# 7_Sensitivity.net
KiCad netlist of a schematic drawn in Altium Designer
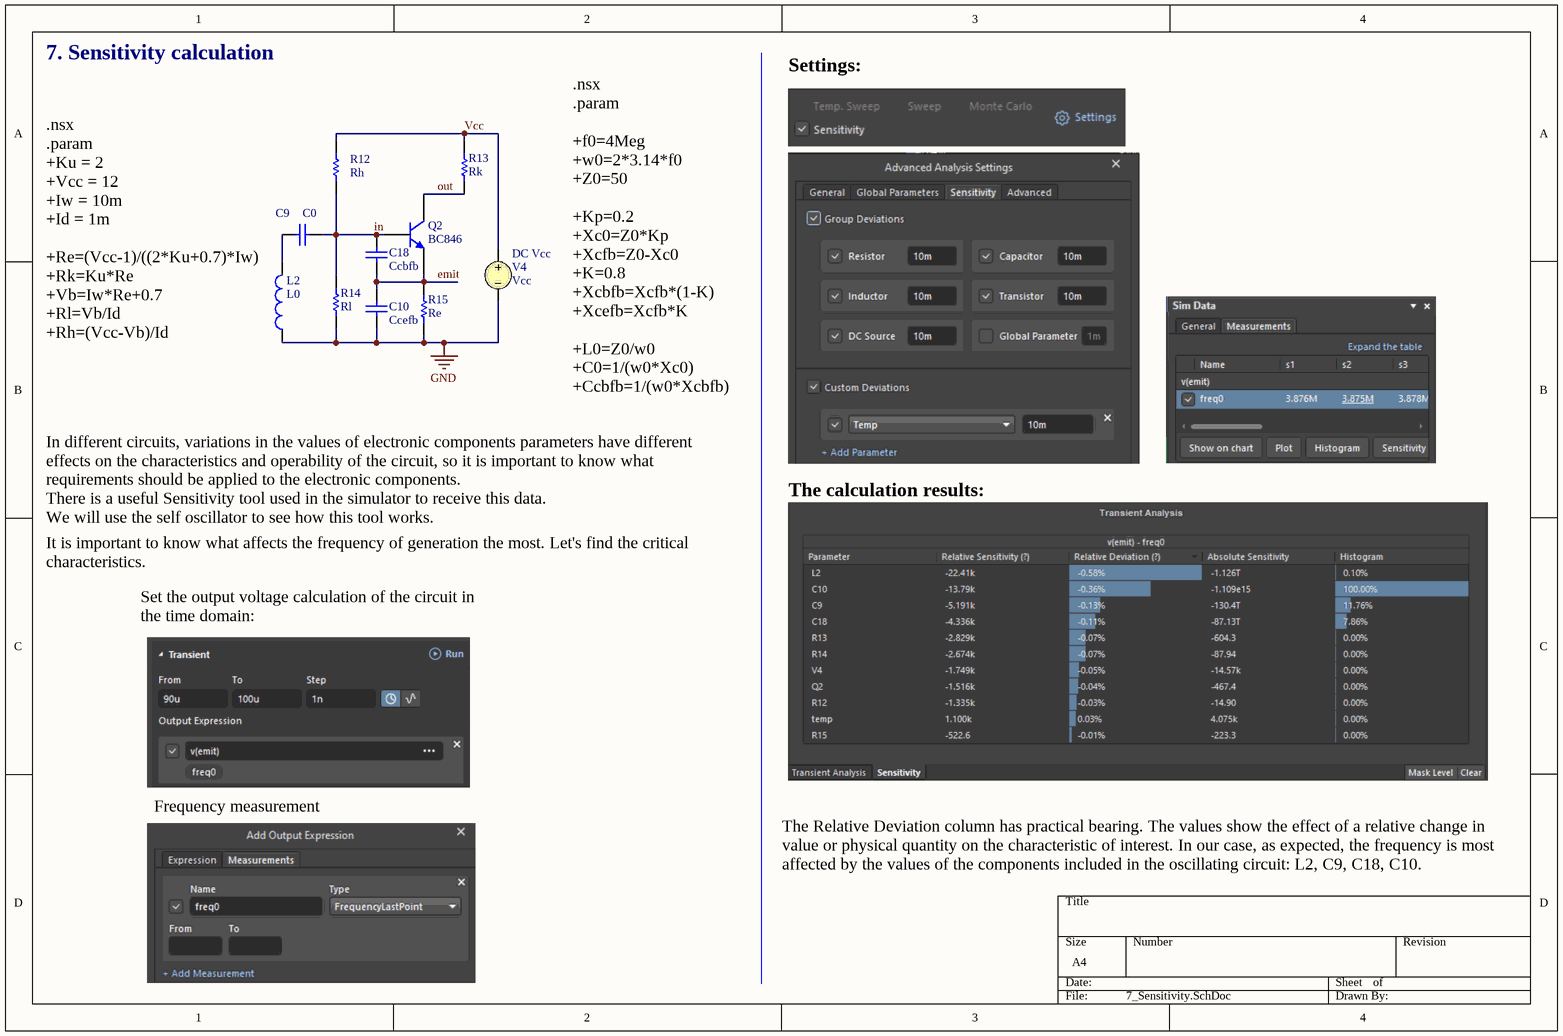
[diagram p0: 7_Sensitivity.SchDoc]

(export (version "E")
  (design (tool "Eeschema 10.0.6"))
  (components
    (comp (ref "C9")
      (value "C0")
      (description "Capacitor")
      (libsource (lib "Simulation Generic Components") (part "Capacitor"))
    )
    (comp (ref "C10")
      (value "Ccefb")
      (description "Capacitor")
      (libsource (lib "Simulation Generic Components") (part "Capacitor"))
    )
    (comp (ref "C18")
      (value "Ccbfb")
      (description "Capacitor")
      (libsource (lib "Simulation Generic Components") (part "Capacitor"))
    )
    (comp (ref "L2")
      (value "L0")
      (description "Inductor")
      (libsource (lib "Simulation Generic Components") (part "Inductor"))
    )
    (comp (ref "Q2")
      (value "BC846")
      (footprint "TO-92A")
      (description "NPN General Purpose Amplifier")
      (fields (field (name "PUBLISHER") "Altium Limited"))
      (libsource (lib "Miscellaneous Devices") (part "2N3904"))
    )
    (comp (ref "R12")
      (value "Rh")
      (description "Resistor")
      (libsource (lib "Simulation Generic Components") (part "Resistor"))
    )
    (comp (ref "R13")
      (value "Rk")
      (description "Resistor")
      (libsource (lib "Simulation Generic Components") (part "Resistor"))
    )
    (comp (ref "R14")
      (value "Rl")
      (description "Resistor")
      (libsource (lib "Simulation Generic Components") (part "Resistor"))
    )
    (comp (ref "R15")
      (value "Re")
      (description "Resistor")
      (libsource (lib "Simulation Generic Components") (part "Resistor"))
    )
    (comp (ref "V4")
      (value "DC Vcc")
      (description "Voltage Source")
      (fields (field (name "ALTIUM_VALUE") "Vcc") (field (name "PUBLISHER") "Altium Limited"))
      (libsource (lib "Simulation Generic Components") (part "VSRC"))
    )
  )
  (nets
    (net (code "1") (name "/Vcc") (class "Default")
      (node (ref "R12") (pin "2") (pinfunction "2_2") (pintype "passive"))
      (node (ref "R13") (pin "2") (pinfunction "2_2") (pintype "passive"))
      (node (ref "V4") (pin "1") (pinfunction "1_1") (pintype "passive"))
    )
    (net (code "2") (name "/emit") (class "Default")
      (node (ref "C10") (pin "2") (pinfunction "2_2") (pintype "passive"))
      (node (ref "C18") (pin "1") (pinfunction "1_1") (pintype "passive"))
      (node (ref "Q2") (pin "1") (pinfunction "E_1") (pintype "passive"))
      (node (ref "R15") (pin "2") (pinfunction "2_2") (pintype "passive"))
    )
    (net (code "3") (name "/in") (class "Default")
      (node (ref "C18") (pin "2") (pinfunction "2_2") (pintype "passive"))
      (node (ref "C9") (pin "2") (pinfunction "2_2") (pintype "passive"))
      (node (ref "Q2") (pin "2") (pinfunction "B_2") (pintype "passive"))
      (node (ref "R12") (pin "1") (pinfunction "1_1") (pintype "passive"))
      (node (ref "R14") (pin "1") (pinfunction "1_1") (pintype "passive"))
    )
    (net (code "4") (name "/out") (class "Default")
      (node (ref "Q2") (pin "3") (pinfunction "C_3") (pintype "passive"))
      (node (ref "R13") (pin "1") (pinfunction "1_1") (pintype "passive"))
    )
    (net (code "5") (name "GND") (class "Default")
      (node (ref "C10") (pin "1") (pinfunction "1_1") (pintype "passive"))
      (node (ref "L2") (pin "1") (pinfunction "1_1") (pintype "passive"))
      (node (ref "R14") (pin "2") (pinfunction "2_2") (pintype "passive"))
      (node (ref "R15") (pin "1") (pinfunction "1_1") (pintype "passive"))
      (node (ref "V4") (pin "2") (pinfunction "2_2") (pintype "passive"))
    )
    (net (code "6") (name "Net-(C9-Pad1)") (class "Default")
      (node (ref "C9") (pin "1") (pinfunction "1_1") (pintype "passive"))
      (node (ref "L2") (pin "2") (pinfunction "2_2") (pintype "passive"))
    )
  )
)
